# BMS.net
KiCad netlist of a schematic drawn in Altium Designer
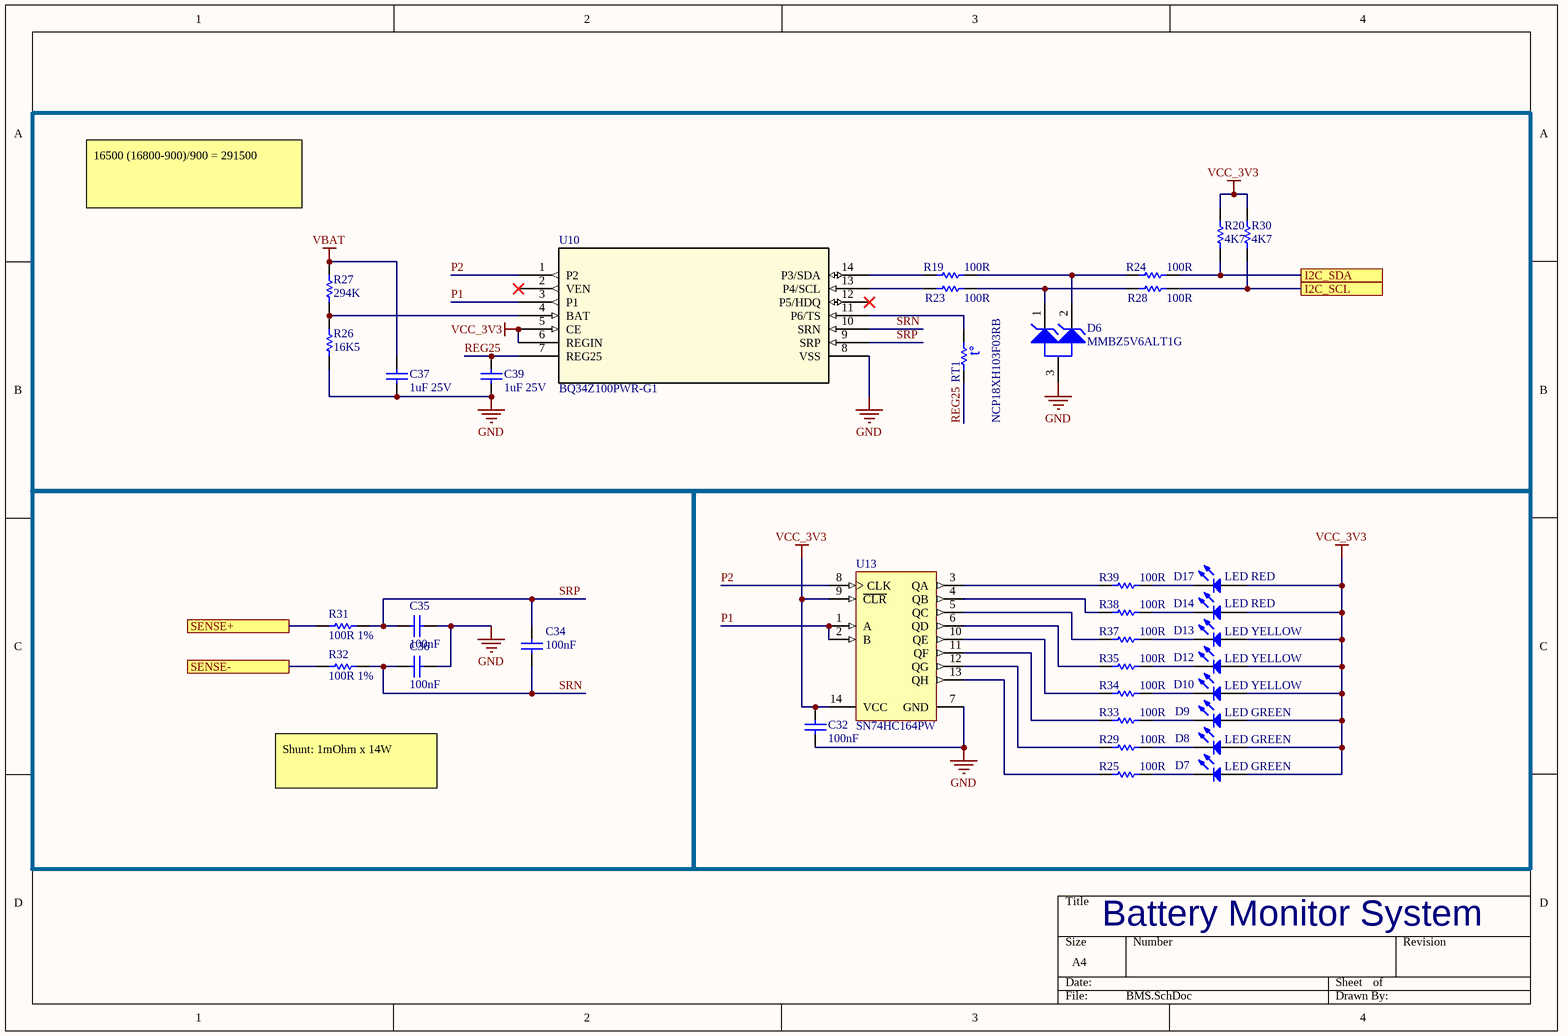
[diagram p0: BMS.SchDoc]

(export (version "E")
  (design (tool "Eeschema 10.0.6"))
  (components
    (comp (ref "C32")
      (value "100nF")
      (footprint "CAPC0603(1608)100_L")
      (description "CAP 100nF 100V ±10% 0603 (1608 Metric) Thickness 1mm SMD")
      (fields (field (name "TOLERANCE") "Â±10%"))
      (libsource (lib "Altium Content Vault") (part "CAP"))
    )
    (comp (ref "C34")
      (value "100nF")
      (footprint "CAPC0603(1608)100_L")
      (description "CAP 100nF 100V ±10% 0603 (1608 Metric) Thickness 1mm SMD")
      (fields (field (name "TOLERANCE") "Â±10%"))
      (libsource (lib "Altium Content Vault") (part "CAP"))
    )
    (comp (ref "C35")
      (value "100nF")
      (footprint "CAPC0603(1608)100_L")
      (description "CAP 100nF 100V ±10% 0603 (1608 Metric) Thickness 1mm SMD")
      (fields (field (name "TOLERANCE") "Â±10%"))
      (libsource (lib "Altium Content Vault") (part "CAP"))
    )
    (comp (ref "C36")
      (value "100nF")
      (footprint "CAPC0603(1608)100_L")
      (description "CAP 100nF 100V ±10% 0603 (1608 Metric) Thickness 1mm SMD")
      (fields (field (name "TOLERANCE") "Â±10%"))
      (libsource (lib "Altium Content Vault") (part "CAP"))
    )
    (comp (ref "C37")
      (value "1uF 25V")
      (footprint "CAPC0603(1608)100_L")
      (description "CAP 1uF 25V ±10% 0603 (1608 Metric) Thickness 1mm SMD")
      (fields (field (name "TOLERANCE") "Â±10%"))
      (libsource (lib "Altium Content Vault") (part "CAP"))
    )
    (comp (ref "C39")
      (value "1uF 25V")
      (footprint "CAPC0603(1608)100_L")
      (description "CAP 1uF 25V ±10% 0603 (1608 Metric) Thickness 1mm SMD")
      (fields (field (name "TOLERANCE") "Â±10%"))
      (libsource (lib "Altium Content Vault") (part "CAP"))
    )
    (comp (ref "D6")
      (value "MMBZ5V6ALT1G")
      (footprint "ONSC-SOT-23-3-318-08_V")
      (fields (field (name "MANUFACTURER") "On Semiconductor"))
      (libsource (lib "Altium Content Vault") (part "ONSC-K1K2A3-3"))
    )
    (comp (ref "D7")
      (value "LED GREEN")
      (footprint "LED_0805")
      (description "led\r\n LTST-C171KRKT")
      (fields
        (field (name "MANUFACTURER") "Lite-On Inc.")
        (field (name "MANUFACTURER PART NUMBER") "LTST-C171KGKT")
      )
      (libsource (lib "CMR_Miscellaneous_Devices") (part "LED0"))
    )
    (comp (ref "D8")
      (value "LED GREEN")
      (footprint "LED_0805")
      (description "led\r\n LTST-C171KRKT")
      (fields
        (field (name "MANUFACTURER") "Lite-On Inc.")
        (field (name "MANUFACTURER PART NUMBER") "LTST-C171KGKT")
      )
      (libsource (lib "CMR_Miscellaneous_Devices") (part "LED0"))
    )
    (comp (ref "D9")
      (value "LED GREEN")
      (footprint "LED_0805")
      (description "led\r\n LTST-C171KRKT")
      (fields
        (field (name "MANUFACTURER") "Lite-On Inc.")
        (field (name "MANUFACTURER PART NUMBER") "LTST-C171KGKT")
      )
      (libsource (lib "CMR_Miscellaneous_Devices") (part "LED0"))
    )
    (comp (ref "D10")
      (value "LED YELLOW")
      (footprint "LED_0805")
      (description "led\r\n LTST-C171KSKT")
      (fields
        (field (name "MANUFACTURER") "Lite-On Inc.")
        (field (name "MANUFACTURER PART NUMBER") "LTST-C171KSKT")
      )
      (libsource (lib "CMR_Miscellaneous_Devices") (part "LED0"))
    )
    (comp (ref "D12")
      (value "LED YELLOW")
      (footprint "LED_0805")
      (description "led\r\n LTST-C171KSKT")
      (fields
        (field (name "MANUFACTURER") "Lite-On Inc.")
        (field (name "MANUFACTURER PART NUMBER") "LTST-C171KSKT")
      )
      (libsource (lib "CMR_Miscellaneous_Devices") (part "LED0"))
    )
    (comp (ref "D13")
      (value "LED YELLOW")
      (footprint "LED_0805")
      (description "led\r\n LTST-C171KSKT")
      (fields
        (field (name "MANUFACTURER") "Lite-On Inc.")
        (field (name "MANUFACTURER PART NUMBER") "LTST-C171KSKT")
      )
      (libsource (lib "CMR_Miscellaneous_Devices") (part "LED0"))
    )
    (comp (ref "D14")
      (value "LED RED")
      (footprint "LED_0805")
      (description "led\r\n LTST-C171KRKT")
      (fields
        (field (name "MANUFACTURER") "Lite-On Inc.")
        (field (name "MANUFACTURER PART NUMBER") "LTST-C171KRKT")
      )
      (libsource (lib "CMR_Miscellaneous_Devices") (part "LED0"))
    )
    (comp (ref "D17")
      (value "LED RED")
      (footprint "LED_0805")
      (description "led\r\n LTST-C171KRKT")
      (fields
        (field (name "MANUFACTURER") "Lite-On Inc.")
        (field (name "MANUFACTURER PART NUMBER") "LTST-C171KRKT")
      )
      (libsource (lib "CMR_Miscellaneous_Devices") (part "LED0"))
    )
    (comp (ref "R19")
      (value "100R")
      (footprint "RESC0603(1608)_L")
      (description "100R 0.1W 1% 0603 (1608 Metric)  SMD")
      (fields (field (name "TOLERANCE") "1 %") (field (name "POWER") "0.1 W"))
      (libsource (lib "Altium Content Vault") (part "RES"))
    )
    (comp (ref "R20")
      (value "4K7")
      (footprint "RESC0603(1608)_L")
      (description "4K7 0.1W 1% 0603 (1608 Metric)  SMD")
      (fields (field (name "POWER") "0.1 W") (field (name "TOLERANCE") "1 %"))
      (libsource (lib "Altium Content Vault") (part "RES"))
    )
    (comp (ref "R23")
      (value "100R")
      (footprint "RESC0603(1608)_L")
      (description "100R 0.1W 1% 0603 (1608 Metric)  SMD")
      (fields (field (name "TOLERANCE") "1 %") (field (name "POWER") "0.1 W"))
      (libsource (lib "Altium Content Vault") (part "RES"))
    )
    (comp (ref "R24")
      (value "100R")
      (footprint "RESC0603(1608)_L")
      (description "100R 0.1W 1% 0603 (1608 Metric)  SMD")
      (fields (field (name "TOLERANCE") "1 %") (field (name "POWER") "0.1 W"))
      (libsource (lib "Altium Content Vault") (part "RES"))
    )
    (comp (ref "R25")
      (value "100R")
      (footprint "RESC0603(1608)_L")
      (description "100R 0.1W 5% 0603 (1608 Metric)  SMD")
      (fields (field (name "TOLERANCE") "5 %") (field (name "POWER") "0.1 W"))
      (libsource (lib "Altium Content Vault") (part "RES"))
    )
    (comp (ref "R26")
      (value "16K5")
      (footprint "RESC0603(1608)_L")
      (description "16K5 0.1W 1% 0603 (1608 Metric)  SMD")
      (fields (field (name "POWER") "0.1 W") (field (name "TOLERANCE") "1 %"))
      (libsource (lib "Altium Content Vault") (part "RES"))
    )
    (comp (ref "R27")
      (value "294K")
      (footprint "RESC0603(1608)_L")
      (description "294K 0.1W 1% 0603 (1608 Metric)  SMD")
      (fields (field (name "POWER") "0.1 W") (field (name "TOLERANCE") "1 %"))
      (libsource (lib "Altium Content Vault") (part "RES"))
    )
    (comp (ref "R28")
      (value "100R")
      (footprint "RESC0603(1608)_L")
      (description "100R 0.1W 1% 0603 (1608 Metric)  SMD")
      (fields (field (name "TOLERANCE") "1 %") (field (name "POWER") "0.1 W"))
      (libsource (lib "Altium Content Vault") (part "RES"))
    )
    (comp (ref "R29")
      (value "100R")
      (footprint "RESC0603(1608)_L")
      (description "100R 0.1W 5% 0603 (1608 Metric)  SMD")
      (fields (field (name "TOLERANCE") "5 %") (field (name "POWER") "0.1 W"))
      (libsource (lib "Altium Content Vault") (part "RES"))
    )
    (comp (ref "R30")
      (value "4K7")
      (footprint "RESC0603(1608)_L")
      (description "4K7 0.1W 1% 0603 (1608 Metric)  SMD")
      (fields (field (name "POWER") "0.1 W") (field (name "TOLERANCE") "1 %"))
      (libsource (lib "Altium Content Vault") (part "RES"))
    )
    (comp (ref "R31")
      (value "100R 1%")
      (footprint "RESC0603(1608)_L")
      (description "100R 0.1W 1% 0603 (1608 Metric)  SMD")
      (fields (field (name "TOLERANCE") "1 %") (field (name "POWER") "0.1 W"))
      (libsource (lib "Altium Content Vault") (part "RES"))
    )
    (comp (ref "R32")
      (value "100R 1%")
      (footprint "RESC0603(1608)_L")
      (description "100R 0.1W 1% 0603 (1608 Metric)  SMD")
      (fields (field (name "TOLERANCE") "1 %") (field (name "POWER") "0.1 W"))
      (libsource (lib "Altium Content Vault") (part "RES"))
    )
    (comp (ref "R33")
      (value "100R")
      (footprint "RESC0603(1608)_L")
      (description "100R 0.1W 5% 0603 (1608 Metric)  SMD")
      (fields (field (name "TOLERANCE") "5 %") (field (name "POWER") "0.1 W"))
      (libsource (lib "Altium Content Vault") (part "RES"))
    )
    (comp (ref "R34")
      (value "100R")
      (footprint "RESC0603(1608)_L")
      (description "100R 0.1W 5% 0603 (1608 Metric)  SMD")
      (fields (field (name "TOLERANCE") "5 %") (field (name "POWER") "0.1 W"))
      (libsource (lib "Altium Content Vault") (part "RES"))
    )
    (comp (ref "R35")
      (value "100R")
      (footprint "RESC0603(1608)_L")
      (description "100R 0.1W 5% 0603 (1608 Metric)  SMD")
      (fields (field (name "TOLERANCE") "5 %") (field (name "POWER") "0.1 W"))
      (libsource (lib "Altium Content Vault") (part "RES"))
    )
    (comp (ref "R37")
      (value "100R")
      (footprint "RESC0603(1608)_L")
      (description "100R 0.1W 5% 0603 (1608 Metric)  SMD")
      (fields (field (name "TOLERANCE") "5 %") (field (name "POWER") "0.1 W"))
      (libsource (lib "Altium Content Vault") (part "RES"))
    )
    (comp (ref "R38")
      (value "100R")
      (footprint "RESC0603(1608)_L")
      (description "100R 0.1W 5% 0603 (1608 Metric)  SMD")
      (fields (field (name "TOLERANCE") "5 %") (field (name "POWER") "0.1 W"))
      (libsource (lib "Altium Content Vault") (part "RES"))
    )
    (comp (ref "R39")
      (value "100R")
      (footprint "RESC0603(1608)_L")
      (description "100R 0.1W 5% 0603 (1608 Metric)  SMD")
      (fields (field (name "TOLERANCE") "5 %") (field (name "POWER") "0.1 W"))
      (libsource (lib "Altium Content Vault") (part "RES"))
    )
    (comp (ref "RT1")
      (value "NCP18XH103F03RB")
      (footprint "MURA-NCP18XH103F03RB-2_V")
      (description "NTC Thermistor, 10 KOhm, +/- 1%, 0.1 W, -40 to 125 degC, 0603 (1608 Metric), RoHS, Tape and Reel")
      (fields (field (name "MANUFACTURER") "Murata"))
      (libsource (lib "Altium Content Vault") (part "MURA-NCP18XH103F03RB-2"))
    )
    (comp (ref "U10")
      (value "BQ34Z100PWR-G1")
      (footprint "PW14")
      (description "No Description Available")
      (fields (field (name "COPYRIGHT") "Copyright (C) 2018 Accelerated Designs. All rights reserved"))
      (libsource (lib "Tauv-Lib") (part "BQ34Z100PWR-G1"))
    )
    (comp (ref "U13")
      (value "SN74HC164PW")
      (footprint "PW0014A_N")
      (description "8-Bit Parallel-Out Serial Shift Registers, PW0014A, TUBE")
      (fields
        (field (name "MANUFACTURER") "Texas Instruments")
        (field (name "GENERIC PART NUMBER") "SN74HC164")
      )
      (libsource (lib "Altium Content Vault") (part "TI-SNX4XXX164X-14"))
    )
  )
  (nets
    (net (code "1") (name "/I2C_SCL") (class "Default")
      (node (ref "R28") (pin "2") (pinfunction "2_2") (pintype "passive"))
      (node (ref "R30") (pin "1") (pinfunction "1_1") (pintype "passive"))
    )
    (net (code "2") (name "/I2C_SDA") (class "Default")
      (node (ref "R20") (pin "1") (pinfunction "1_1") (pintype "passive"))
      (node (ref "R24") (pin "2") (pinfunction "2_2") (pintype "passive"))
    )
    (net (code "3") (name "/P1") (class "Default")
      (node (ref "U10") (pin "3") (pinfunction "P1_3") (pintype "output"))
      (node (ref "U13") (pin "1") (pinfunction "A_1") (pintype "input"))
      (node (ref "U13") (pin "2") (pinfunction "B_2") (pintype "input"))
    )
    (net (code "4") (name "/P2") (class "Default")
      (node (ref "U10") (pin "1") (pinfunction "P2_1") (pintype "output"))
      (node (ref "U13") (pin "8") (pinfunction "CLK_8") (pintype "input"))
    )
    (net (code "5") (name "/REG25") (class "Default")
      (node (ref "C39") (pin "2") (pinfunction "2_2") (pintype "passive"))
      (node (ref "RT1") (pin "1") (pinfunction "1_1") (pintype "passive"))
      (node (ref "U10") (pin "7") (pinfunction "REG25_7") (pintype "power_in"))
    )
    (net (code "6") (name "/SENSE+") (class "Default")
      (node (ref "R31") (pin "1") (pinfunction "1_1") (pintype "passive"))
    )
    (net (code "7") (name "/SENSE-") (class "Default")
      (node (ref "R32") (pin "1") (pinfunction "1_1") (pintype "passive"))
    )
    (net (code "8") (name "/SRN") (class "Default")
      (node (ref "C34") (pin "1") (pinfunction "1_1") (pintype "passive"))
      (node (ref "C36") (pin "2") (pinfunction "2_2") (pintype "passive"))
      (node (ref "R32") (pin "2") (pinfunction "2_2") (pintype "passive"))
      (node (ref "U10") (pin "10") (pinfunction "SRN_10") (pintype "input"))
    )
    (net (code "9") (name "/SRP") (class "Default")
      (node (ref "C34") (pin "2") (pinfunction "2_2") (pintype "passive"))
      (node (ref "C35") (pin "2") (pinfunction "2_2") (pintype "passive"))
      (node (ref "R31") (pin "2") (pinfunction "2_2") (pintype "passive"))
      (node (ref "U10") (pin "9") (pinfunction "SRP_9") (pintype "input"))
    )
    (net (code "10") (name "GND") (class "Default")
      (node (ref "C32") (pin "1") (pinfunction "1_1") (pintype "passive"))
      (node (ref "C35") (pin "1") (pinfunction "1_1") (pintype "passive"))
      (node (ref "C36") (pin "1") (pinfunction "1_1") (pintype "passive"))
      (node (ref "C37") (pin "1") (pinfunction "1_1") (pintype "passive"))
      (node (ref "C39") (pin "1") (pinfunction "1_1") (pintype "passive"))
      (node (ref "D6") (pin "3") (pinfunction "A_3") (pintype "passive"))
      (node (ref "R26") (pin "1") (pinfunction "1_1") (pintype "passive"))
      (node (ref "U10") (pin "8") (pinfunction "VSS_8") (pintype "power_in"))
      (node (ref "U13") (pin "7") (pinfunction "GND_7") (pintype "power_in"))
    )
    (net (code "11") (name "Net-(D6-K1)") (class "Default")
      (node (ref "D6") (pin "1") (pinfunction "K1_1") (pintype "passive"))
      (node (ref "R23") (pin "2") (pinfunction "2_2") (pintype "passive"))
      (node (ref "R28") (pin "1") (pinfunction "1_1") (pintype "passive"))
    )
    (net (code "12") (name "Net-(D6-K2)") (class "Default")
      (node (ref "D6") (pin "2") (pinfunction "K2_2") (pintype "passive"))
      (node (ref "R19") (pin "2") (pinfunction "2_2") (pintype "passive"))
      (node (ref "R24") (pin "1") (pinfunction "1_1") (pintype "passive"))
    )
    (net (code "13") (name "Net-(D7-K)") (class "Default")
      (node (ref "D7") (pin "1") (pinfunction "K_1") (pintype "passive"))
      (node (ref "R25") (pin "2") (pinfunction "2_2") (pintype "passive"))
    )
    (net (code "14") (name "Net-(D8-K)") (class "Default")
      (node (ref "D8") (pin "1") (pinfunction "K_1") (pintype "passive"))
      (node (ref "R29") (pin "2") (pinfunction "2_2") (pintype "passive"))
    )
    (net (code "15") (name "Net-(D9-K)") (class "Default")
      (node (ref "D9") (pin "1") (pinfunction "K_1") (pintype "passive"))
      (node (ref "R33") (pin "2") (pinfunction "2_2") (pintype "passive"))
    )
    (net (code "16") (name "Net-(D10-K)") (class "Default")
      (node (ref "D10") (pin "1") (pinfunction "K_1") (pintype "passive"))
      (node (ref "R34") (pin "2") (pinfunction "2_2") (pintype "passive"))
    )
    (net (code "17") (name "Net-(D12-K)") (class "Default")
      (node (ref "D12") (pin "1") (pinfunction "K_1") (pintype "passive"))
      (node (ref "R35") (pin "2") (pinfunction "2_2") (pintype "passive"))
    )
    (net (code "18") (name "Net-(D13-K)") (class "Default")
      (node (ref "D13") (pin "1") (pinfunction "K_1") (pintype "passive"))
      (node (ref "R37") (pin "2") (pinfunction "2_2") (pintype "passive"))
    )
    (net (code "19") (name "Net-(D14-K)") (class "Default")
      (node (ref "D14") (pin "1") (pinfunction "K_1") (pintype "passive"))
      (node (ref "R38") (pin "2") (pinfunction "2_2") (pintype "passive"))
    )
    (net (code "20") (name "Net-(D17-K)") (class "Default")
      (node (ref "D17") (pin "1") (pinfunction "K_1") (pintype "passive"))
      (node (ref "R39") (pin "2") (pinfunction "2_2") (pintype "passive"))
    )
    (net (code "21") (name "Net-(U10-BAT)") (class "Default")
      (node (ref "R26") (pin "2") (pinfunction "2_2") (pintype "passive"))
      (node (ref "R27") (pin "1") (pinfunction "1_1") (pintype "passive"))
      (node (ref "U10") (pin "4") (pinfunction "BAT_4") (pintype "input"))
    )
    (net (code "22") (name "Net-(U10-P3{slash}SDA)") (class "Default")
      (node (ref "R19") (pin "1") (pinfunction "1_1") (pintype "passive"))
      (node (ref "U10") (pin "14") (pinfunction "P3/SDA_14") (pintype "bidirectional"))
    )
    (net (code "23") (name "Net-(U10-P4{slash}SCL)") (class "Default")
      (node (ref "R23") (pin "1") (pinfunction "1_1") (pintype "passive"))
      (node (ref "U10") (pin "13") (pinfunction "P4/SCL_13") (pintype "input"))
    )
    (net (code "24") (name "Net-(U10-P6{slash}TS)") (class "Default")
      (node (ref "RT1") (pin "2") (pinfunction "2_2") (pintype "passive"))
      (node (ref "U10") (pin "11") (pinfunction "P6/TS_11") (pintype "input"))
    )
    (net (code "25") (name "Net-(U13-QA)") (class "Default")
      (node (ref "R39") (pin "1") (pinfunction "1_1") (pintype "passive"))
      (node (ref "U13") (pin "3") (pinfunction "QA_3") (pintype "output"))
    )
    (net (code "26") (name "Net-(U13-QB)") (class "Default")
      (node (ref "R38") (pin "1") (pinfunction "1_1") (pintype "passive"))
      (node (ref "U13") (pin "4") (pinfunction "QB_4") (pintype "output"))
    )
    (net (code "27") (name "Net-(U13-QC)") (class "Default")
      (node (ref "R37") (pin "1") (pinfunction "1_1") (pintype "passive"))
      (node (ref "U13") (pin "5") (pinfunction "QC_5") (pintype "output"))
    )
    (net (code "28") (name "Net-(U13-QD)") (class "Default")
      (node (ref "R35") (pin "1") (pinfunction "1_1") (pintype "passive"))
      (node (ref "U13") (pin "6") (pinfunction "QD_6") (pintype "output"))
    )
    (net (code "29") (name "Net-(U13-QE)") (class "Default")
      (node (ref "R34") (pin "1") (pinfunction "1_1") (pintype "passive"))
      (node (ref "U13") (pin "10") (pinfunction "QE_10") (pintype "output"))
    )
    (net (code "30") (name "Net-(U13-QF)") (class "Default")
      (node (ref "R33") (pin "1") (pinfunction "1_1") (pintype "passive"))
      (node (ref "U13") (pin "11") (pinfunction "QF_11") (pintype "output"))
    )
    (net (code "31") (name "Net-(U13-QG)") (class "Default")
      (node (ref "R29") (pin "1") (pinfunction "1_1") (pintype "passive"))
      (node (ref "U13") (pin "12") (pinfunction "QG_12") (pintype "output"))
    )
    (net (code "32") (name "Net-(U13-QH)") (class "Default")
      (node (ref "R25") (pin "1") (pinfunction "1_1") (pintype "passive"))
      (node (ref "U13") (pin "13") (pinfunction "QH_13") (pintype "output"))
    )
    (net (code "33") (name "VBAT") (class "Default")
      (node (ref "C37") (pin "2") (pinfunction "2_2") (pintype "passive"))
      (node (ref "R27") (pin "2") (pinfunction "2_2") (pintype "passive"))
    )
    (net (code "34") (name "VCC_3V3") (class "Default")
      (node (ref "C32") (pin "2") (pinfunction "2_2") (pintype "passive"))
      (node (ref "D10") (pin "2") (pinfunction "A_2") (pintype "passive"))
      (node (ref "D12") (pin "2") (pinfunction "A_2") (pintype "passive"))
      (node (ref "D13") (pin "2") (pinfunction "A_2") (pintype "passive"))
      (node (ref "D14") (pin "2") (pinfunction "A_2") (pintype "passive"))
      (node (ref "D17") (pin "2") (pinfunction "A_2") (pintype "passive"))
      (node (ref "D7") (pin "2") (pinfunction "A_2") (pintype "passive"))
      (node (ref "D8") (pin "2") (pinfunction "A_2") (pintype "passive"))
      (node (ref "D9") (pin "2") (pinfunction "A_2") (pintype "passive"))
      (node (ref "R20") (pin "2") (pinfunction "2_2") (pintype "passive"))
      (node (ref "R30") (pin "2") (pinfunction "2_2") (pintype "passive"))
      (node (ref "U10") (pin "5") (pinfunction "CE_5") (pintype "input"))
      (node (ref "U10") (pin "6") (pinfunction "REGIN_6") (pintype "power_in"))
      (node (ref "U13") (pin "14") (pinfunction "VCC_14") (pintype "power_in"))
      (node (ref "U13") (pin "9") (pinfunction "~{CLR}_9") (pintype "input"))
    )
    (net (code "35") (name "unconnected-(U10-P5{slash}HDQ-Pad12)") (class "Default")
      (node (ref "U10") (pin "12") (pinfunction "P5/HDQ_12") (pintype "bidirectional+no_connect"))
    )
    (net (code "36") (name "unconnected-(U10-VEN-Pad2)") (class "Default")
      (node (ref "U10") (pin "2") (pinfunction "VEN_2") (pintype "output+no_connect"))
    )
  )
)
